# ADC.net
KiCad netlist of a schematic drawn in Altium Designer
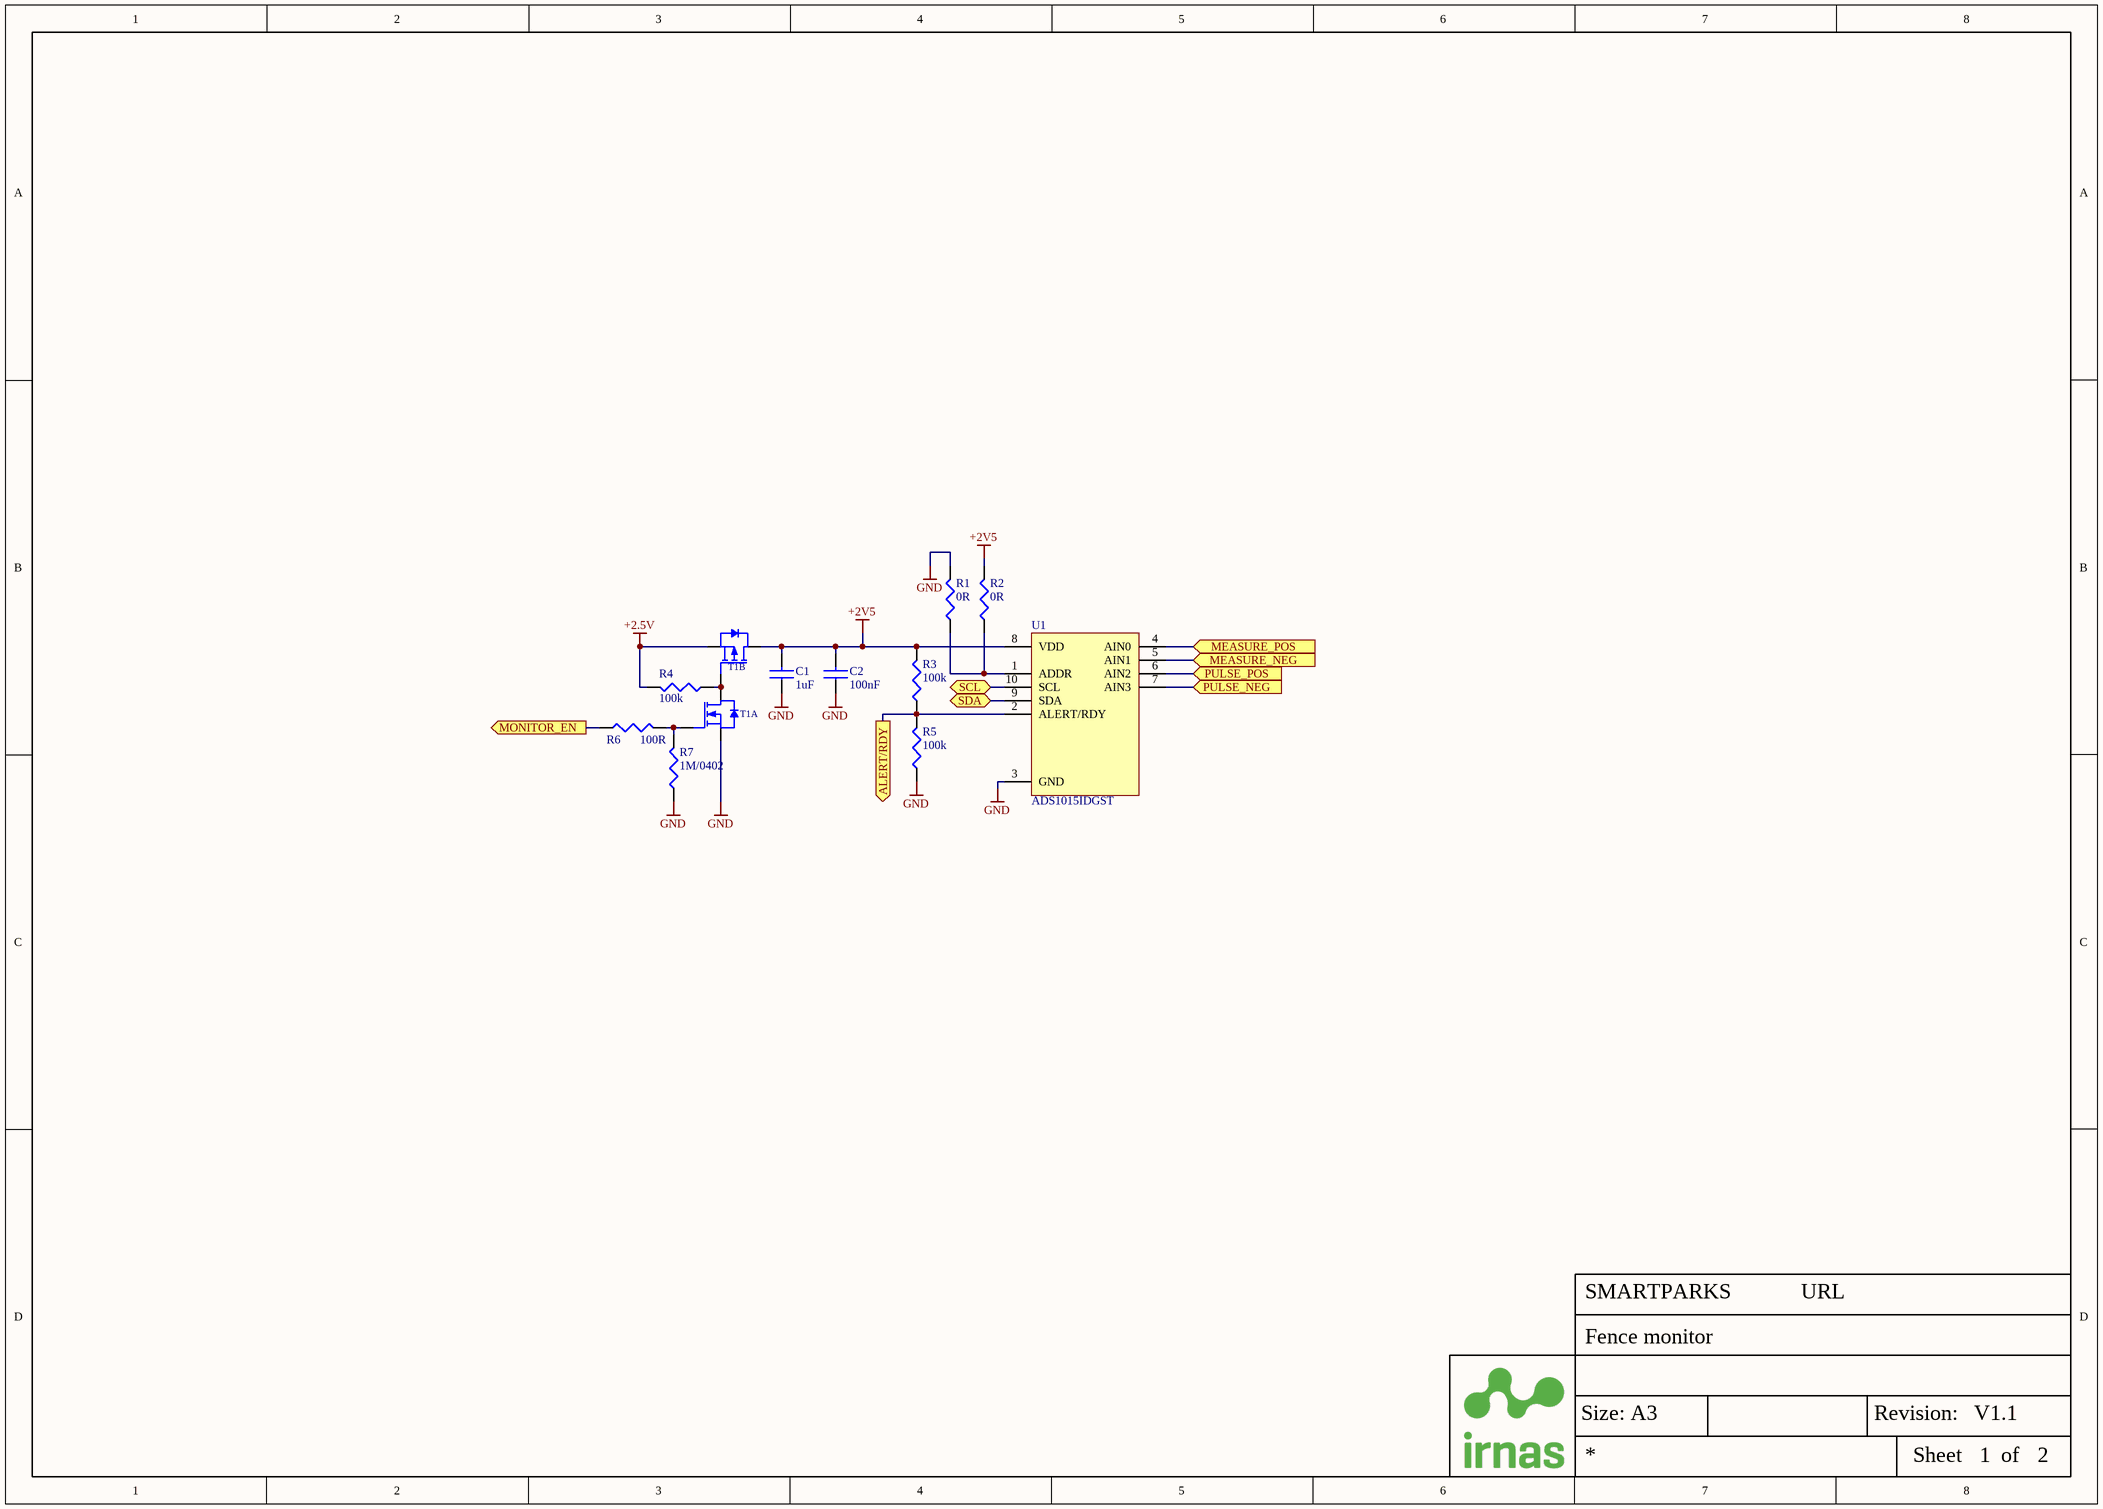
[diagram p0: ADC.SchDoc]

(export (version "E")
  (design (tool "Eeschema 10.0.6"))
  (components
    (comp (ref "C1")
      (value "1uF")
      (footprint "CAP0402")
      (description "CAP CER 1UF 10V 20% X5R 0402")
      (fields
        (field (name "MANUFACTURER") "Murata")
        (field (name "MANUFACTURER PART NUMBER") "GRM155R61A105ME15D")
      )
      (libsource (lib "Passive") (part "C - 1uF/0402"))
    )
    (comp (ref "C2")
      (value "100nF")
      (footprint "CAP0402")
      (fields
        (field (name "MANUFACTURER") "Multicomp")
        (field (name "MANUFACTURER PART NUMBER") "MC0402X104J160CT")
        (field (name "TOLERANCE") "5%")
      )
      (libsource (lib "Passive") (part "C - 100nF/0402"))
    )
    (comp (ref "R1")
      (value "0R")
      (footprint "RES0402")
      (description "RESISTOR, 0402, 0R, ANTI SULFURATION")
      (fields
        (field (name "MANUFACTURER") "Multicomp")
        (field (name "MANUFACTURER PART NUMBER") "MCMR04X000PTL")
      )
      (libsource (lib "Passive") (part "R - 0R/0402"))
    )
    (comp (ref "R2")
      (value "0R")
      (footprint "RES0402")
      (description "RESISTOR, 0402, 0R, ANTI SULFURATION")
      (fields
        (field (name "MANUFACTURER") "Multicomp")
        (field (name "MANUFACTURER PART NUMBER") "MCMR04X000PTL")
      )
      (libsource (lib "Passive") (part "R - 0R/0402"))
    )
    (comp (ref "R3")
      (value "100k")
      (footprint "RES0402")
      (description "MULTICOMP   MCWR04X1003FTL   RES, THICK FILM, 100KOHM, 1%, 0.0625W")
      (fields
        (field (name "MANUFACTURER") "Multicomp")
        (field (name "MANUFACTURER PART NUMBER") "MCWR04X1003FTL")
      )
      (libsource (lib "Passive") (part "R - 100k/0402"))
    )
    (comp (ref "R4")
      (value "100k")
      (footprint "RES0402")
      (description "100KOHM, 1%, 0.0625W")
      (fields
        (field (name "MANUFACTURER") "Multicomp")
        (field (name "MANUFACTURER PART NUMBER") "MCWR04X1003FTL")
      )
      (libsource (lib "Passive") (part "R - 100k/0402"))
    )
    (comp (ref "R5")
      (value "100k")
      (footprint "RES0402")
      (description "MULTICOMP   MCWR04X1003FTL   RES, THICK FILM, 100KOHM, 1%, 0.0625W")
      (fields
        (field (name "MANUFACTURER") "Multicomp")
        (field (name "MANUFACTURER PART NUMBER") "MCWR04X1003FTL")
      )
      (libsource (lib "Passive") (part "R - 100k/0402"))
    )
    (comp (ref "R6")
      (value "100R")
      (footprint "RES0402")
      (description "100 ohm, 50 V, 0402 [1005 Metric], 62.5 mW,  1%")
      (fields
        (field (name "MANUFACTURER") "Multicomp")
        (field (name "MANUFACTURER PART NUMBER") "MCMR04X1000FTL")
      )
      (libsource (lib "Passive") (part "R - 100R/0402"))
    )
    (comp (ref "R7")
      (value "1M/0402")
      (footprint "RES0402")
      (description "MCMR04X1004FTL RES, 1M, 1%, 0.0625W, 0402, THICK FILM")
      (fields
        (field (name "MANUFACTURER") "MULTICOMP")
        (field (name "MANUFACTURER PART NUMBER") "MC0063W060311M")
      )
      (libsource (lib "Passive") (part "R - 1M/0402"))
    )
    (comp (ref "T1")
      (value "VT6M1T2CR")
      (footprint "VMT6")
      (description "Dual MOSFET, N and P Channel, 100 mA, 20 V, 2.5 ohm, 4.5 V, 1 V")
      (fields (field (name "AUTHOR") "Ciril Golob"))
      (libsource (lib "Active") (part "T_M - VT6M1T2CR"))
    )
    (comp (ref "U1")
      (value "ADS1015IDGST")
      (footprint "VSSOP-10")
      (description "Analogue to Digital Converter, 12 bit, 3.3 kSPS, Differential, Single Ended, I2C, Single")
      (fields (field (name "MANUFACTURER") "TEXAS INSTRUMENTS"))
      (libsource (lib "Active") (part "ADC - ADS1015IDGST"))
    )
  )
  (nets
    (net (code "1") (name "+2.5V") (class "Default")
      (node (ref "R4") (pin "2") (pinfunction "2_2") (pintype "passive"))
      (node (ref "T1") (pin "4") (pinfunction "S2_4") (pintype "passive"))
    )
    (net (code "2") (name "+2V5") (class "Default")
      (node (ref "C1") (pin "2") (pinfunction "2_2") (pintype "passive"))
      (node (ref "C2") (pin "2") (pinfunction "2_2") (pintype "passive"))
      (node (ref "R2") (pin "2") (pinfunction "2_2") (pintype "passive"))
      (node (ref "R3") (pin "2") (pinfunction "2_2") (pintype "passive"))
      (node (ref "T1") (pin "3") (pinfunction "D2_3") (pintype "passive"))
      (node (ref "U1") (pin "8") (pinfunction "VDD_8") (pintype "passive"))
    )
    (net (code "3") (name "/ALERT{slash}RDY") (class "Default")
      (node (ref "R3") (pin "1") (pinfunction "1_1") (pintype "passive"))
      (node (ref "R5") (pin "2") (pinfunction "2_2") (pintype "passive"))
      (node (ref "U1") (pin "2") (pinfunction "ALERT/RDY_2") (pintype "passive"))
    )
    (net (code "4") (name "/MEASURE_NEG") (class "Default")
      (node (ref "U1") (pin "5") (pinfunction "AIN1_5") (pintype "passive"))
    )
    (net (code "5") (name "/MEASURE_POS") (class "Default")
      (node (ref "U1") (pin "4") (pinfunction "AIN0_4") (pintype "passive"))
    )
    (net (code "6") (name "/MONITOR_EN") (class "Default")
      (node (ref "R6") (pin "1") (pinfunction "1_1") (pintype "passive"))
    )
    (net (code "7") (name "/PULSE_NEG") (class "Default")
      (node (ref "U1") (pin "7") (pinfunction "AIN3_7") (pintype "passive"))
    )
    (net (code "8") (name "/PULSE_POS") (class "Default")
      (node (ref "U1") (pin "6") (pinfunction "AIN2_6") (pintype "passive"))
    )
    (net (code "9") (name "/SCL") (class "Default")
      (node (ref "U1") (pin "10") (pinfunction "SCL_10") (pintype "passive"))
    )
    (net (code "10") (name "/SDA") (class "Default")
      (node (ref "U1") (pin "9") (pinfunction "SDA_9") (pintype "passive"))
    )
    (net (code "11") (name "GND") (class "Default")
      (node (ref "C1") (pin "1") (pinfunction "1_1") (pintype "passive"))
      (node (ref "C2") (pin "1") (pinfunction "1_1") (pintype "passive"))
      (node (ref "R1") (pin "2") (pinfunction "2_2") (pintype "passive"))
      (node (ref "R5") (pin "1") (pinfunction "1_1") (pintype "passive"))
      (node (ref "R7") (pin "1") (pinfunction "1_1") (pintype "passive"))
      (node (ref "T1") (pin "1") (pinfunction "S1_1") (pintype "passive"))
      (node (ref "U1") (pin "3") (pinfunction "GND_3") (pintype "passive"))
    )
    (net (code "12") (name "Net-(T1A-D1)") (class "Default")
      (node (ref "R4") (pin "1") (pinfunction "1_1") (pintype "passive"))
      (node (ref "T1") (pin "5") (pinfunction "G2_5") (pintype "passive"))
      (node (ref "T1") (pin "6") (pinfunction "D1_6") (pintype "passive"))
    )
    (net (code "13") (name "Net-(T1A-G1)") (class "Default")
      (node (ref "R6") (pin "2") (pinfunction "2_2") (pintype "passive"))
      (node (ref "R7") (pin "2") (pinfunction "2_2") (pintype "passive"))
      (node (ref "T1") (pin "2") (pinfunction "G1_2") (pintype "passive"))
    )
    (net (code "14") (name "Net-(U1-ADDR)") (class "Default")
      (node (ref "R1") (pin "1") (pinfunction "1_1") (pintype "passive"))
      (node (ref "R2") (pin "1") (pinfunction "1_1") (pintype "passive"))
      (node (ref "U1") (pin "1") (pinfunction "ADDR_1") (pintype "passive"))
    )
  )
)
